# Main.net
KiCad netlist of a schematic drawn in Altium Designer
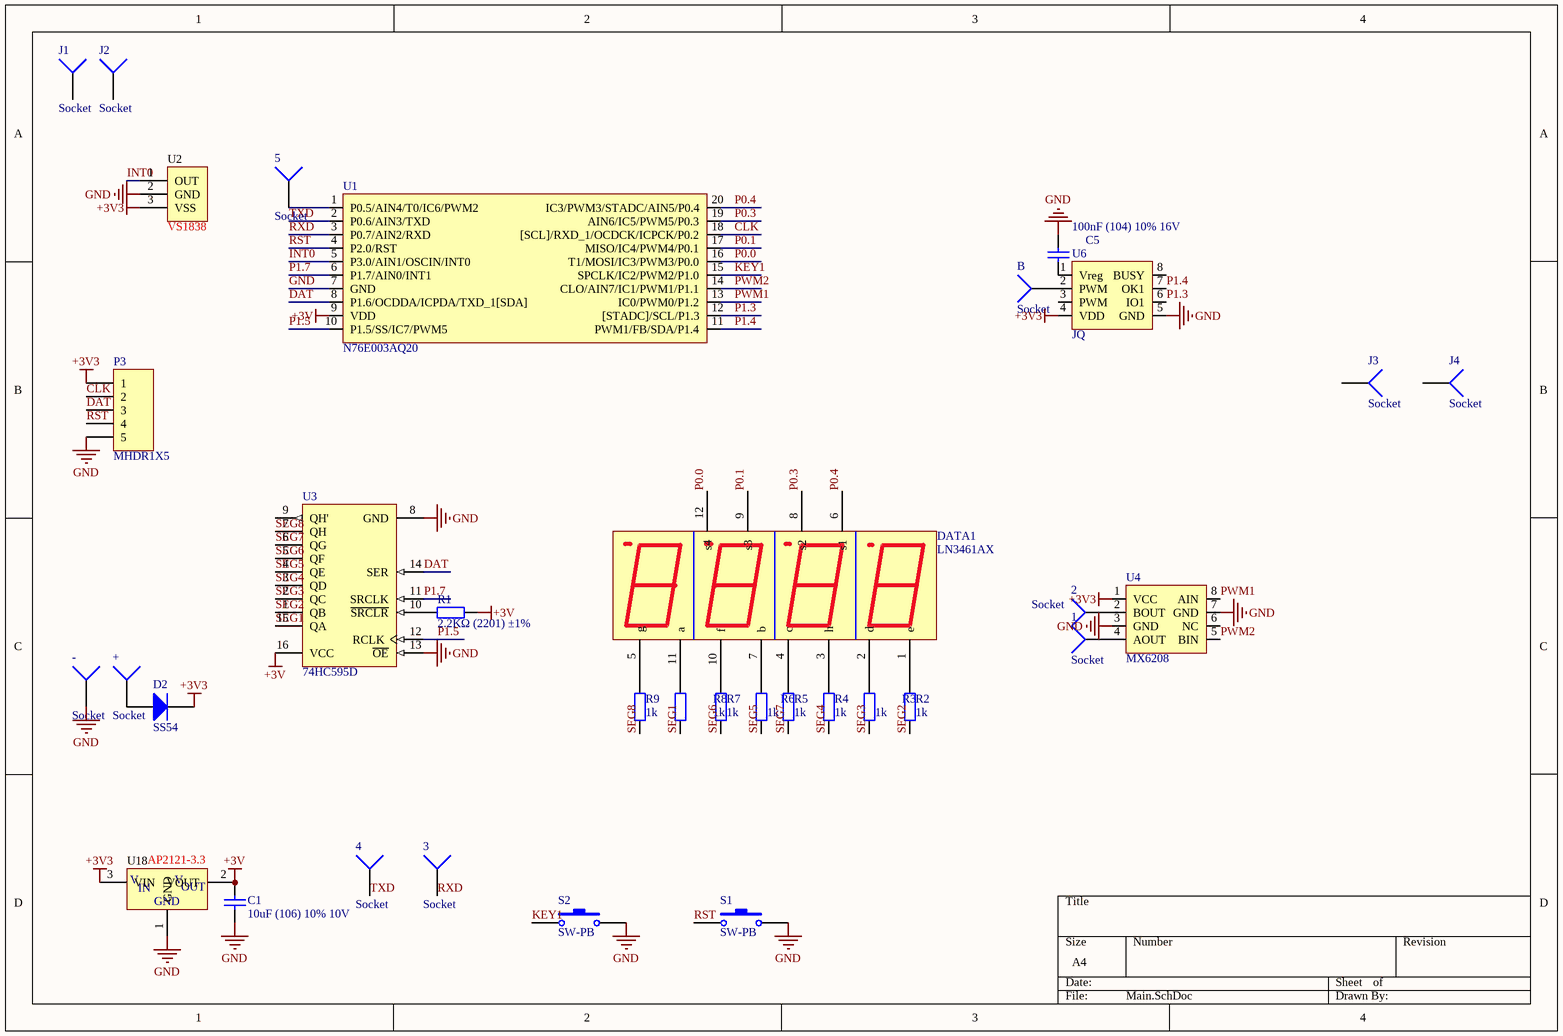
[diagram p0: Main.SchDoc]

(export (version "E")
  (design (tool "Eeschema 10.0.6"))
  (components
    (comp (ref "+")
      (value "Socket")
      (footprint "MODULE-PAD$2F$3")
      (fields (field (name "PUBLISHER") "Altium Limited"))
      (libsource (lib "Miscellaneous Connectors") (part "Socket"))
    )
    (comp (ref "-")
      (value "Socket")
      (footprint "MODULE-PAD$2F$3")
      (fields (field (name "PUBLISHER") "Altium Limited"))
      (libsource (lib "Miscellaneous Connectors") (part "Socket"))
    )
    (comp (ref "1")
      (value "Socket")
      (footprint "MODULE-PAD$2F$3")
      (fields (field (name "PUBLISHER") "Altium Limited"))
      (libsource (lib "Miscellaneous Connectors") (part "Socket"))
    )
    (comp (ref "2")
      (value "Socket")
      (footprint "MODULE-PAD$2F$3")
      (fields (field (name "PUBLISHER") "Altium Limited"))
      (libsource (lib "Miscellaneous Connectors") (part "Socket"))
    )
    (comp (ref "3")
      (value "Socket")
      (footprint "MODULE-PAD$2F$3")
      (fields (field (name "PUBLISHER") "Altium Limited"))
      (libsource (lib "Miscellaneous Connectors") (part "Socket"))
    )
    (comp (ref "4")
      (value "Socket")
      (footprint "MODULE-PAD$2F$3")
      (fields (field (name "PUBLISHER") "Altium Limited"))
      (libsource (lib "Miscellaneous Connectors") (part "Socket"))
    )
    (comp (ref "5")
      (value "Socket")
      (footprint "MODULE-PAD$2F$3")
      (fields (field (name "PUBLISHER") "Altium Limited"))
      (libsource (lib "Miscellaneous Connectors") (part "Socket"))
    )
    (comp (ref "B")
      (value "Socket")
      (footprint "MODULE-PAD$2F$3")
      (fields (field (name "PUBLISHER") "Altium Limited"))
      (libsource (lib "Miscellaneous Connectors") (part "Socket"))
    )
    (comp (ref "C1")
      (value "10uF (106) 10% 10V")
      (footprint "0603_C")
      (description "贴片电容")
      (libsource (lib "Miscellaneous Devices LC") (part "0603 10uF (106) 10% 10V"))
    )
    (comp (ref "C5")
      (value "100nF (104) 10% 16V")
      (footprint "0402_C")
      (description "贴片电容")
      (libsource (lib "Miscellaneous Devices LC") (part "0402 100nF (104) 10% 16V"))
    )
    (comp (ref "D2")
      (value "SS54")
      (footprint "SMA(DO-214AC)_S1")
      (description "二极管")
      (libsource (lib "LC") (part "SMA(DO-214AC) SS54"))
    )
    (comp (ref "DATA1")
      (value "LN3461AX")
      (footprint "DIP12:DISP2")
      (description "data?")
      (libsource (lib "*") (part "DATA04"))
    )
    (comp (ref "J1")
      (value "Socket")
      (footprint "FPAD_1")
      (fields (field (name "PUBLISHER") "Altium Limited"))
      (libsource (lib "Miscellaneous Connectors") (part "Socket"))
    )
    (comp (ref "J2")
      (value "Socket")
      (footprint "FPAD_1")
      (fields (field (name "PUBLISHER") "Altium Limited"))
      (libsource (lib "Miscellaneous Connectors") (part "Socket"))
    )
    (comp (ref "J3")
      (value "Socket")
      (footprint "FPAD_1")
      (fields (field (name "PUBLISHER") "Altium Limited"))
      (libsource (lib "Miscellaneous Connectors") (part "Socket"))
    )
    (comp (ref "J4")
      (value "Socket")
      (footprint "FPAD_1")
      (fields (field (name "PUBLISHER") "Altium Limited"))
      (libsource (lib "Miscellaneous Connectors") (part "Socket"))
    )
    (comp (ref "P3")
      (value "MHDR1X5")
      (footprint "MHDR1X5")
      (description "Header, 5-Pin")
      (fields (field (name "PUBLISHER") "Altium Limited"))
      (libsource (lib "Miscellaneous Connectors") (part "MHDR1X5"))
    )
    (comp (ref "R1")
      (value "2.2KΩ (2201) ±1%")
      (footprint "0402_R")
      (description "贴片电阻")
      (libsource (lib "") (part "0402 2.2KΩ (2201) 1%_1"))
    )
    (comp (ref "R2")
      (value "1k")
      (footprint "0402_R")
      (description "贴片电阻")
      (libsource (lib "LC") (part "0402 2.2KΩ (2201) 1%"))
    )
    (comp (ref "R3")
      (value "1k")
      (footprint "0402_R")
      (description "贴片电阻")
      (libsource (lib "LC") (part "0402 2.2KΩ (2201) 1%"))
    )
    (comp (ref "R4")
      (value "1k")
      (footprint "0402_R")
      (description "贴片电阻")
      (libsource (lib "LC") (part "0402 2.2KΩ (2201) 1%"))
    )
    (comp (ref "R5")
      (value "1k")
      (footprint "0402_R")
      (description "贴片电阻")
      (libsource (lib "LC") (part "0402 2.2KΩ (2201) 1%"))
    )
    (comp (ref "R6")
      (value "1k")
      (footprint "0402_R")
      (description "贴片电阻")
      (libsource (lib "LC") (part "0402 2.2KΩ (2201) 1%"))
    )
    (comp (ref "R7")
      (value "1k")
      (footprint "0402_R")
      (description "贴片电阻")
      (libsource (lib "LC") (part "0402 2.2KΩ (2201) 1%"))
    )
    (comp (ref "R8")
      (value "1k")
      (footprint "0402_R")
      (description "贴片电阻")
      (libsource (lib "LC") (part "0402 2.2KΩ (2201) 1%"))
    )
    (comp (ref "R9")
      (value "1k")
      (footprint "0402_R")
      (description "贴片电阻")
      (libsource (lib "LC") (part "0402 2.2KΩ (2201) 1%"))
    )
    (comp (ref "S1")
      (value "SW-PB")
      (footprint "SB1$2F$2")
      (description "Switch")
      (fields (field (name "PUBLISHER") "Altium Limited"))
      (libsource (lib "Miscellaneous Devices") (part "SW-PB"))
    )
    (comp (ref "S2")
      (value "SW-PB")
      (footprint "SB1$2F$2")
      (description "Switch")
      (fields (field (name "PUBLISHER") "Altium Limited"))
      (libsource (lib "Miscellaneous Devices") (part "SW-PB"))
    )
    (comp (ref "U1")
      (value "N76E003AQ20")
      (footprint "TSSOP20")
      (libsource (lib "童金吕个人库") (part "N76E003AQ20"))
    )
    (comp (ref "U2")
      (value "VS1838")
      (footprint "LF0038Q")
      (description "1838 接收头 VS1838 VS1838B")
      (libsource (lib "甲壳虫Geek-InSect_1") (part "RF"))
    )
    (comp (ref "U3")
      (value "74HC595D")
      (footprint "SOIC-16_150mil")
      (description "74系列逻辑芯片")
      (libsource (lib "LC") (part "74HC595D"))
    )
    (comp (ref "U4") (value "MX6208") (footprint "SOIC-8_150mil") (libsource (lib "Main") (part "MX6208")))
    (comp (ref "U6") (value "JQ") (footprint "SOIC-8_150mil") (libsource (lib "MiniCar") (part "JQ")))
    (comp (ref "U18")
      (value "AP2121-3.3")
      (footprint "SOT-23")
      (description "3V LDO")
      (libsource (lib "wllibs") (part "AP2121-3"))
    )
  )
  (nets
    (net (code "1") (name "+3V") (class "Default")
      (node (ref "C1") (pin "2") (pinfunction "2_2") (pintype "passive"))
      (node (ref "R1") (pin "2") (pinfunction "2_2") (pintype "passive"))
      (node (ref "U1") (pin "9") (pinfunction "VDD_9") (pintype "passive"))
      (node (ref "U18") (pin "2") (pinfunction "VOUT_2") (pintype "passive"))
      (node (ref "U3") (pin "16") (pinfunction "VCC_16") (pintype "power_in"))
    )
    (net (code "2") (name "+3V3") (class "Default")
      (node (ref "D2") (pin "2") (pinfunction "K_2") (pintype "passive"))
      (node (ref "P3") (pin "1") (pinfunction "1_1") (pintype "passive"))
      (node (ref "U18") (pin "3") (pinfunction "VIN_3") (pintype "passive"))
      (node (ref "U2") (pin "3") (pinfunction "VSS_3") (pintype "passive"))
      (node (ref "U4") (pin "1") (pinfunction "VCC_1") (pintype "passive"))
      (node (ref "U6") (pin "4") (pinfunction "VDD_4") (pintype "passive"))
    )
    (net (code "3") (name "/CLK") (class "Default")
      (node (ref "P3") (pin "2") (pinfunction "2_2") (pintype "passive"))
      (node (ref "U1") (pin "18") (pinfunction "[SCL]/RXD_1/OCDCK/ICPCK/P0.2_18") (pintype "passive"))
    )
    (net (code "4") (name "/DAT") (class "Default")
      (node (ref "P3") (pin "3") (pinfunction "3_3") (pintype "passive"))
      (node (ref "U1") (pin "8") (pinfunction "P1.6/OCDDA/ICPDA/TXD_1[SDA]_8") (pintype "passive"))
      (node (ref "U3") (pin "14") (pinfunction "SER_14") (pintype "input"))
    )
    (net (code "5") (name "/INT0") (class "Default")
      (node (ref "U1") (pin "5") (pinfunction "P3.0/AIN1/OSCIN/INT0_5") (pintype "passive"))
      (node (ref "U2") (pin "1") (pinfunction "OUT_1") (pintype "passive"))
    )
    (net (code "6") (name "/KEY1") (class "Default")
      (node (ref "S2") (pin "1") (pinfunction "1_1") (pintype "passive"))
      (node (ref "U1") (pin "15") (pinfunction "SPCLK/IC2/PWM2/P1.0_15") (pintype "passive"))
    )
    (net (code "7") (name "/P0.0") (class "Default")
      (node (ref "DATA1") (pin "12") (pinfunction "s4_12") (pintype "passive"))
      (node (ref "U1") (pin "16") (pinfunction "T1/MOSI/IC3/PWM3/P0.0_16") (pintype "passive"))
    )
    (net (code "8") (name "/P0.1") (class "Default")
      (node (ref "DATA1") (pin "9") (pinfunction "s3_9") (pintype "passive"))
      (node (ref "U1") (pin "17") (pinfunction "MISO/IC4/PWM4/P0.1_17") (pintype "passive"))
    )
    (net (code "9") (name "/P0.3") (class "Default")
      (node (ref "DATA1") (pin "8") (pinfunction "s2_8") (pintype "passive"))
      (node (ref "U1") (pin "19") (pinfunction "AIN6/IC5/PWM5/P0.3_19") (pintype "passive"))
    )
    (net (code "10") (name "/P0.4") (class "Default")
      (node (ref "DATA1") (pin "6") (pinfunction "s1_6") (pintype "passive"))
      (node (ref "U1") (pin "20") (pinfunction "IC3/PWM3/STADC/AIN5/P0.4_20") (pintype "passive"))
    )
    (net (code "11") (name "/P1.3") (class "Default")
      (node (ref "U1") (pin "12") (pinfunction "[STADC]/SCL/P1.3_12") (pintype "passive"))
      (node (ref "U6") (pin "6") (pinfunction "IO1_6") (pintype "passive"))
    )
    (net (code "12") (name "/P1.4") (class "Default")
      (node (ref "U1") (pin "11") (pinfunction "PWM1/FB/SDA/P1.4_11") (pintype "passive"))
      (node (ref "U6") (pin "7") (pinfunction "OK1_7") (pintype "passive"))
    )
    (net (code "13") (name "/P1.5") (class "Default")
      (node (ref "U1") (pin "10") (pinfunction "P1.5/SS/IC7/PWM5_10") (pintype "passive"))
      (node (ref "U3") (pin "12") (pinfunction "RCLK_12") (pintype "input"))
    )
    (net (code "14") (name "/P1.7") (class "Default")
      (node (ref "U1") (pin "6") (pinfunction "P1.7/AIN0/INT1_6") (pintype "passive"))
      (node (ref "U3") (pin "11") (pinfunction "SRCLK_11") (pintype "input"))
    )
    (net (code "15") (name "/PWM1") (class "Default")
      (node (ref "U1") (pin "13") (pinfunction "IC0/PWM0/P1.2_13") (pintype "passive"))
      (node (ref "U4") (pin "8") (pinfunction "AIN_8") (pintype "passive"))
    )
    (net (code "16") (name "/PWM2") (class "Default")
      (node (ref "U1") (pin "14") (pinfunction "CLO/AIN7/IC1/PWM1/P1.1_14") (pintype "passive"))
      (node (ref "U4") (pin "5") (pinfunction "BIN_5") (pintype "passive"))
    )
    (net (code "17") (name "/RST") (class "Default")
      (node (ref "P3") (pin "4") (pinfunction "4_4") (pintype "passive"))
      (node (ref "S1") (pin "1") (pinfunction "1_1") (pintype "passive"))
      (node (ref "U1") (pin "4") (pinfunction "P2.0/RST_4") (pintype "passive"))
    )
    (net (code "18") (name "/RXD") (class "Default")
      (node (ref "3") (pin "1") (pinfunction "1_1") (pintype "passive"))
      (node (ref "U1") (pin "3") (pinfunction "P0.7/AIN2/RXD_3") (pintype "passive"))
    )
    (net (code "19") (name "/SEG1") (class "Default")
      (node (ref "R8") (pin "2") (pinfunction "2_2") (pintype "passive"))
      (node (ref "U3") (pin "15") (pinfunction "QA_15") (pintype "tri_state"))
    )
    (net (code "20") (name "/SEG2") (class "Default")
      (node (ref "R2") (pin "2") (pinfunction "2_2") (pintype "passive"))
      (node (ref "U3") (pin "1") (pinfunction "QB_1") (pintype "tri_state"))
    )
    (net (code "21") (name "/SEG3") (class "Default")
      (node (ref "R3") (pin "2") (pinfunction "2_2") (pintype "passive"))
      (node (ref "U3") (pin "2") (pinfunction "QC_2") (pintype "tri_state"))
    )
    (net (code "22") (name "/SEG4") (class "Default")
      (node (ref "R4") (pin "2") (pinfunction "2_2") (pintype "passive"))
      (node (ref "U3") (pin "3") (pinfunction "QD_3") (pintype "tri_state"))
    )
    (net (code "23") (name "/SEG5") (class "Default")
      (node (ref "R6") (pin "2") (pinfunction "2_2") (pintype "passive"))
      (node (ref "U3") (pin "4") (pinfunction "QE_4") (pintype "tri_state"))
    )
    (net (code "24") (name "/SEG6") (class "Default")
      (node (ref "R7") (pin "2") (pinfunction "2_2") (pintype "passive"))
      (node (ref "U3") (pin "5") (pinfunction "QF_5") (pintype "tri_state"))
    )
    (net (code "25") (name "/SEG7") (class "Default")
      (node (ref "R5") (pin "2") (pinfunction "2_2") (pintype "passive"))
      (node (ref "U3") (pin "6") (pinfunction "QG_6") (pintype "tri_state"))
    )
    (net (code "26") (name "/SEG8") (class "Default")
      (node (ref "R9") (pin "2") (pinfunction "2_2") (pintype "passive"))
      (node (ref "U3") (pin "7") (pinfunction "QH_7") (pintype "tri_state"))
    )
    (net (code "27") (name "/TXD") (class "Default")
      (node (ref "4") (pin "1") (pinfunction "1_1") (pintype "passive"))
      (node (ref "U1") (pin "2") (pinfunction "P0.6/AIN3/TXD_2") (pintype "passive"))
    )
    (net (code "28") (name "GND") (class "Default")
      (node (ref "-") (pin "1") (pinfunction "1_1") (pintype "passive"))
      (node (ref "C1") (pin "1") (pinfunction "1_1") (pintype "passive"))
      (node (ref "C5") (pin "2") (pinfunction "2_2") (pintype "passive"))
      (node (ref "P3") (pin "5") (pinfunction "5_5") (pintype "passive"))
      (node (ref "S1") (pin "2") (pinfunction "2_2") (pintype "passive"))
      (node (ref "S2") (pin "2") (pinfunction "2_2") (pintype "passive"))
      (node (ref "U1") (pin "7") (pinfunction "GND_7") (pintype "passive"))
      (node (ref "U18") (pin "1") (pinfunction "GND_1") (pintype "passive"))
      (node (ref "U2") (pin "2") (pinfunction "GND_2") (pintype "passive"))
      (node (ref "U3") (pin "13") (pinfunction "~{OE}_13") (pintype "input"))
      (node (ref "U3") (pin "8") (pinfunction "GND_8") (pintype "power_in"))
      (node (ref "U4") (pin "3") (pinfunction "GND_3") (pintype "passive"))
      (node (ref "U4") (pin "7") (pinfunction "GND_7") (pintype "passive"))
      (node (ref "U6") (pin "5") (pinfunction "GND_5") (pintype "passive"))
    )
    (net (code "29") (name "Net-(B-Pad1)") (class "Default")
      (node (ref "B") (pin "1") (pinfunction "1_1") (pintype "passive"))
      (node (ref "U6") (pin "2") (pinfunction "PWM_2") (pintype "passive"))
    )
    (net (code "30") (name "Net-(D2-A)") (class "Default")
      (node (ref "+") (pin "1") (pinfunction "1_1") (pintype "passive"))
      (node (ref "D2") (pin "1") (pinfunction "A_1") (pintype "passive"))
    )
    (net (code "31") (name "Net-(DATA1-a)") (class "Default")
      (node (ref "DATA1") (pin "11") (pinfunction "a_11") (pintype "passive"))
      (node (ref "R8") (pin "1") (pinfunction "1_1") (pintype "passive"))
    )
    (net (code "32") (name "Net-(DATA1-b)") (class "Default")
      (node (ref "DATA1") (pin "7") (pinfunction "b_7") (pintype "passive"))
      (node (ref "R6") (pin "1") (pinfunction "1_1") (pintype "passive"))
    )
    (net (code "33") (name "Net-(DATA1-c)") (class "Default")
      (node (ref "DATA1") (pin "4") (pinfunction "c_4") (pintype "passive"))
      (node (ref "R5") (pin "1") (pinfunction "1_1") (pintype "passive"))
    )
    (net (code "34") (name "Net-(DATA1-d)") (class "Default")
      (node (ref "DATA1") (pin "2") (pinfunction "d_2") (pintype "passive"))
      (node (ref "R3") (pin "1") (pinfunction "1_1") (pintype "passive"))
    )
    (net (code "35") (name "Net-(DATA1-e)") (class "Default")
      (node (ref "DATA1") (pin "1") (pinfunction "e_1") (pintype "passive"))
      (node (ref "R2") (pin "1") (pinfunction "1_1") (pintype "passive"))
    )
    (net (code "36") (name "Net-(DATA1-f)") (class "Default")
      (node (ref "DATA1") (pin "10") (pinfunction "f_10") (pintype "passive"))
      (node (ref "R7") (pin "1") (pinfunction "1_1") (pintype "passive"))
    )
    (net (code "37") (name "Net-(DATA1-g)") (class "Default")
      (node (ref "DATA1") (pin "5") (pinfunction "g_5") (pintype "passive"))
      (node (ref "R9") (pin "1") (pinfunction "1_1") (pintype "passive"))
    )
    (net (code "38") (name "Net-(DATA1-h)") (class "Default")
      (node (ref "DATA1") (pin "3") (pinfunction "h_3") (pintype "passive"))
      (node (ref "R4") (pin "1") (pinfunction "1_1") (pintype "passive"))
    )
    (net (code "39") (name "Net-(U1-P0.5{slash}AIN4{slash}T0{slash}IC6{slash}PWM2)") (class "Default")
      (node (ref "5") (pin "1") (pinfunction "1_1") (pintype "passive"))
      (node (ref "U1") (pin "1") (pinfunction "P0.5/AIN4/T0/IC6/PWM2_1") (pintype "passive"))
    )
    (net (code "40") (name "Net-(U3-~{SRCLR})") (class "Default")
      (node (ref "R1") (pin "1") (pinfunction "1_1") (pintype "passive"))
      (node (ref "U3") (pin "10") (pinfunction "~{SRCLR}_10") (pintype "input"))
    )
    (net (code "41") (name "Net-(U4-AOUT)") (class "Default")
      (node (ref "1") (pin "1") (pinfunction "1_1") (pintype "passive"))
      (node (ref "U4") (pin "4") (pinfunction "AOUT_4") (pintype "passive"))
    )
    (net (code "42") (name "Net-(U4-BOUT)") (class "Default")
      (node (ref "2") (pin "1") (pinfunction "1_1") (pintype "passive"))
      (node (ref "U4") (pin "2") (pinfunction "BOUT_2") (pintype "passive"))
    )
    (net (code "43") (name "Net-(U6-Vreg)") (class "Default")
      (node (ref "C5") (pin "1") (pinfunction "1_1") (pintype "passive"))
      (node (ref "U6") (pin "1") (pinfunction "Vreg_1") (pintype "passive"))
    )
    (net (code "44") (name "unconnected-(J1-Pad1)") (class "Default")
      (node (ref "J1") (pin "1") (pinfunction "1_1") (pintype "passive"))
    )
    (net (code "45") (name "unconnected-(J2-Pad1)") (class "Default")
      (node (ref "J2") (pin "1") (pinfunction "1_1") (pintype "passive"))
    )
    (net (code "46") (name "unconnected-(J3-Pad1)") (class "Default")
      (node (ref "J3") (pin "1") (pinfunction "1_1") (pintype "passive"))
    )
    (net (code "47") (name "unconnected-(J4-Pad1)") (class "Default")
      (node (ref "J4") (pin "1") (pinfunction "1_1") (pintype "passive"))
    )
    (net (code "48") (name "unconnected-(U3-QH'-Pad9)") (class "Default")
      (node (ref "U3") (pin "9") (pinfunction "QH'_9") (pintype "output"))
    )
    (net (code "49") (name "unconnected-(U4-NC-Pad6)") (class "Default")
      (node (ref "U4") (pin "6") (pinfunction "NC_6") (pintype "passive"))
    )
    (net (code "50") (name "unconnected-(U6-BUSY-Pad8)") (class "Default")
      (node (ref "U6") (pin "8") (pinfunction "BUSY_8") (pintype "passive"))
    )
    (net (code "51") (name "unconnected-(U6-PWM-Pad3)") (class "Default")
      (node (ref "U6") (pin "3") (pinfunction "PWM_3") (pintype "passive"))
    )
  )
)
